# Kill_Switch.net
KiCad netlist of a schematic drawn in Altium Designer
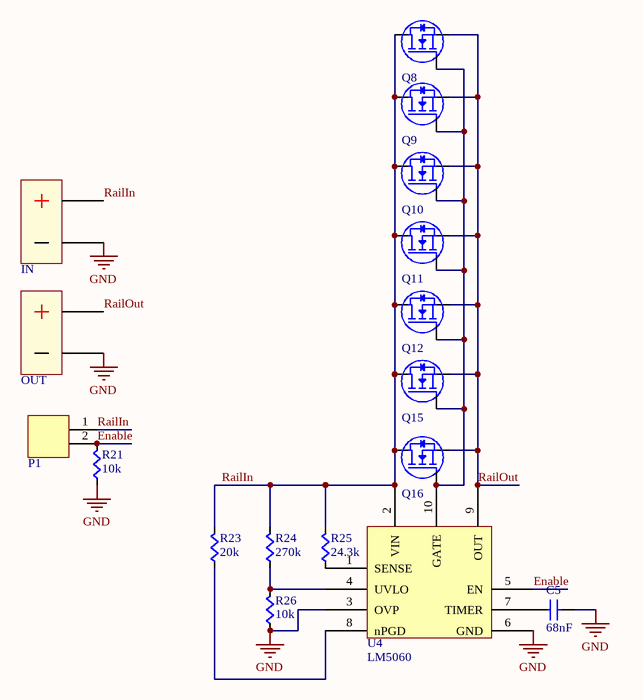
[diagram p0: Kill Switch.SchDoc]

(export (version "E")
  (design (tool "Eeschema 10.0.6"))
  (components
    (comp (ref "C5")
      (value "68nF")
      (footprint "CAPC0603")
      (fields (field (name "Comment") "Cap"))
      (libsource (lib "SubjuGator8") (part "Cap"))
    )
    (comp (ref "IN")
      (value "BATWIRE")
      (footprint "BATWIRE12")
      (description "Two large gauge leads soldered directly to the board.")
      (libsource (lib "SubjuGator8") (part "BATWIRE"))
    )
    (comp (ref "OUT")
      (value "BATWIRE")
      (footprint "BATWIRE12")
      (description "Two large gauge leads soldered directly to the board.")
      (libsource (lib "SubjuGator8") (part "BATWIRE"))
    )
    (comp (ref "P1")
      (value "2-pin Vert Sherlock")
      (footprint "MOLEX-HDR-1X2-SHERLOCK-VERT")
      (libsource (lib "SubjuGator8") (part "MOLEX-HDR-1x2-SHERLOCK_VERT"))
    )
    (comp (ref "Q8")
      (value "CSD19502Q5B")
      (footprint "CSD19502Q5B")
      (description "NEXFET Power MOSFET")
      (libsource (lib "SubjuGator8") (part "CSD19502Q5B"))
    )
    (comp (ref "Q9")
      (value "CSD19502Q5B")
      (footprint "CSD19502Q5B")
      (description "NEXFET Power MOSFET")
      (libsource (lib "SubjuGator8") (part "CSD19502Q5B"))
    )
    (comp (ref "Q10")
      (value "CSD19502Q5B")
      (footprint "CSD19502Q5B")
      (description "NEXFET Power MOSFET")
      (libsource (lib "SubjuGator8") (part "CSD19502Q5B"))
    )
    (comp (ref "Q11")
      (value "CSD19502Q5B")
      (footprint "CSD19502Q5B")
      (description "NEXFET Power MOSFET")
      (libsource (lib "SubjuGator8") (part "CSD19502Q5B"))
    )
    (comp (ref "Q12")
      (value "CSD19502Q5B")
      (footprint "CSD19502Q5B")
      (description "NEXFET Power MOSFET")
      (libsource (lib "SubjuGator8") (part "CSD19502Q5B"))
    )
    (comp (ref "Q15")
      (value "CSD19502Q5B")
      (footprint "CSD19502Q5B")
      (description "NEXFET Power MOSFET")
      (libsource (lib "SubjuGator8") (part "CSD19502Q5B"))
    )
    (comp (ref "Q16")
      (value "CSD19502Q5B")
      (footprint "CSD19502Q5B")
      (description "NEXFET Power MOSFET")
      (libsource (lib "SubjuGator8") (part "CSD19502Q5B"))
    )
    (comp (ref "R21")
      (value "10k")
      (footprint "RES0603")
      (fields (field (name "Comment") "Res"))
      (libsource (lib "SubjuGator8") (part "Res"))
    )
    (comp (ref "R23")
      (value "20k")
      (footprint "RES0603")
      (fields (field (name "Comment") "Res"))
      (libsource (lib "SubjuGator8") (part "Res"))
    )
    (comp (ref "R24")
      (value "270k")
      (footprint "RES0603")
      (fields (field (name "Comment") "Res"))
      (libsource (lib "SubjuGator8") (part "Res"))
    )
    (comp (ref "R25")
      (value "24.3k")
      (footprint "RES0603")
      (fields (field (name "Comment") "Res"))
      (libsource (lib "SubjuGator8") (part "Res"))
    )
    (comp (ref "R26")
      (value "10k")
      (footprint "RES0603")
      (fields (field (name "Comment") "Res"))
      (libsource (lib "SubjuGator8") (part "Res"))
    )
    (comp (ref "U4")
      (value "LM5060")
      (footprint "LM5060")
      (description "Hotswap Controller")
      (libsource (lib "SubjuGator8") (part "LM5060"))
    )
  )
  (nets
    (net (code "1") (name "/Enable") (class "Default")
      (node (ref "P1") (pin "2") (pinfunction "2_2") (pintype "passive"))
      (node (ref "R21") (pin "1") (pinfunction "A_1") (pintype "passive"))
      (node (ref "U4") (pin "5") (pinfunction "EN_5") (pintype "passive"))
    )
    (net (code "2") (name "/RailIn") (class "Default")
      (node (ref "IN") (pin "+") (pinfunction "+_+") (pintype "power_in"))
      (node (ref "P1") (pin "1") (pinfunction "1_1") (pintype "passive"))
      (node (ref "Q10") (pin "D") (pinfunction "D_D") (pintype "passive"))
      (node (ref "Q11") (pin "D") (pinfunction "D_D") (pintype "passive"))
      (node (ref "Q12") (pin "D") (pinfunction "D_D") (pintype "passive"))
      (node (ref "Q15") (pin "D") (pinfunction "D_D") (pintype "passive"))
      (node (ref "Q16") (pin "D") (pinfunction "D_D") (pintype "passive"))
      (node (ref "Q8") (pin "D") (pinfunction "D_D") (pintype "passive"))
      (node (ref "Q9") (pin "D") (pinfunction "D_D") (pintype "passive"))
      (node (ref "R23") (pin "1") (pinfunction "A_1") (pintype "passive"))
      (node (ref "R24") (pin "1") (pinfunction "A_1") (pintype "passive"))
      (node (ref "R25") (pin "1") (pinfunction "A_1") (pintype "passive"))
      (node (ref "U4") (pin "2") (pinfunction "VIN_2") (pintype "passive"))
    )
    (net (code "3") (name "/RailOut") (class "Default")
      (node (ref "OUT") (pin "+") (pinfunction "+_+") (pintype "power_in"))
      (node (ref "Q10") (pin "S") (pinfunction "S_S") (pintype "passive"))
      (node (ref "Q11") (pin "S") (pinfunction "S_S") (pintype "passive"))
      (node (ref "Q12") (pin "S") (pinfunction "S_S") (pintype "passive"))
      (node (ref "Q15") (pin "S") (pinfunction "S_S") (pintype "passive"))
      (node (ref "Q16") (pin "S") (pinfunction "S_S") (pintype "passive"))
      (node (ref "Q8") (pin "S") (pinfunction "S_S") (pintype "passive"))
      (node (ref "Q9") (pin "S") (pinfunction "S_S") (pintype "passive"))
      (node (ref "U4") (pin "9") (pinfunction "OUT_9") (pintype "passive"))
    )
    (net (code "4") (name "GND") (class "Default")
      (node (ref "C5") (pin "2") (pinfunction "B_2") (pintype "passive"))
      (node (ref "IN") (pin "-") (pinfunction "-_-") (pintype "power_in"))
      (node (ref "OUT") (pin "-") (pinfunction "-_-") (pintype "power_in"))
      (node (ref "R21") (pin "2") (pinfunction "B_2") (pintype "passive"))
      (node (ref "R26") (pin "2") (pinfunction "B_2") (pintype "passive"))
      (node (ref "U4") (pin "3") (pinfunction "OVP_3") (pintype "passive"))
      (node (ref "U4") (pin "6") (pinfunction "GND_6") (pintype "passive"))
    )
    (net (code "5") (name "Net-(C5-A)") (class "Default")
      (node (ref "C5") (pin "1") (pinfunction "A_1") (pintype "passive"))
      (node (ref "U4") (pin "7") (pinfunction "TIMER_7") (pintype "passive"))
    )
    (net (code "6") (name "Net-(R23-B)") (class "Default")
      (node (ref "R23") (pin "2") (pinfunction "B_2") (pintype "passive"))
      (node (ref "U4") (pin "8") (pinfunction "nPGD_8") (pintype "passive"))
    )
    (net (code "7") (name "Net-(R24-B)") (class "Default")
      (node (ref "R24") (pin "2") (pinfunction "B_2") (pintype "passive"))
      (node (ref "R26") (pin "1") (pinfunction "A_1") (pintype "passive"))
      (node (ref "U4") (pin "4") (pinfunction "UVLO_4") (pintype "passive"))
    )
    (net (code "8") (name "Net-(R25-B)") (class "Default")
      (node (ref "R25") (pin "2") (pinfunction "B_2") (pintype "passive"))
      (node (ref "U4") (pin "1") (pinfunction "SENSE_1") (pintype "passive"))
    )
    (net (code "9") (name "Net-(U4-GATE)") (class "Default")
      (node (ref "Q10") (pin "G") (pinfunction "G_G") (pintype "passive"))
      (node (ref "Q11") (pin "G") (pinfunction "G_G") (pintype "passive"))
      (node (ref "Q12") (pin "G") (pinfunction "G_G") (pintype "passive"))
      (node (ref "Q15") (pin "G") (pinfunction "G_G") (pintype "passive"))
      (node (ref "Q16") (pin "G") (pinfunction "G_G") (pintype "passive"))
      (node (ref "Q8") (pin "G") (pinfunction "G_G") (pintype "passive"))
      (node (ref "Q9") (pin "G") (pinfunction "G_G") (pintype "passive"))
      (node (ref "U4") (pin "10") (pinfunction "GATE_10") (pintype "passive"))
    )
  )
)
